# rf_txmix.net
KiCad netlist of a schematic drawn in Altium Designer
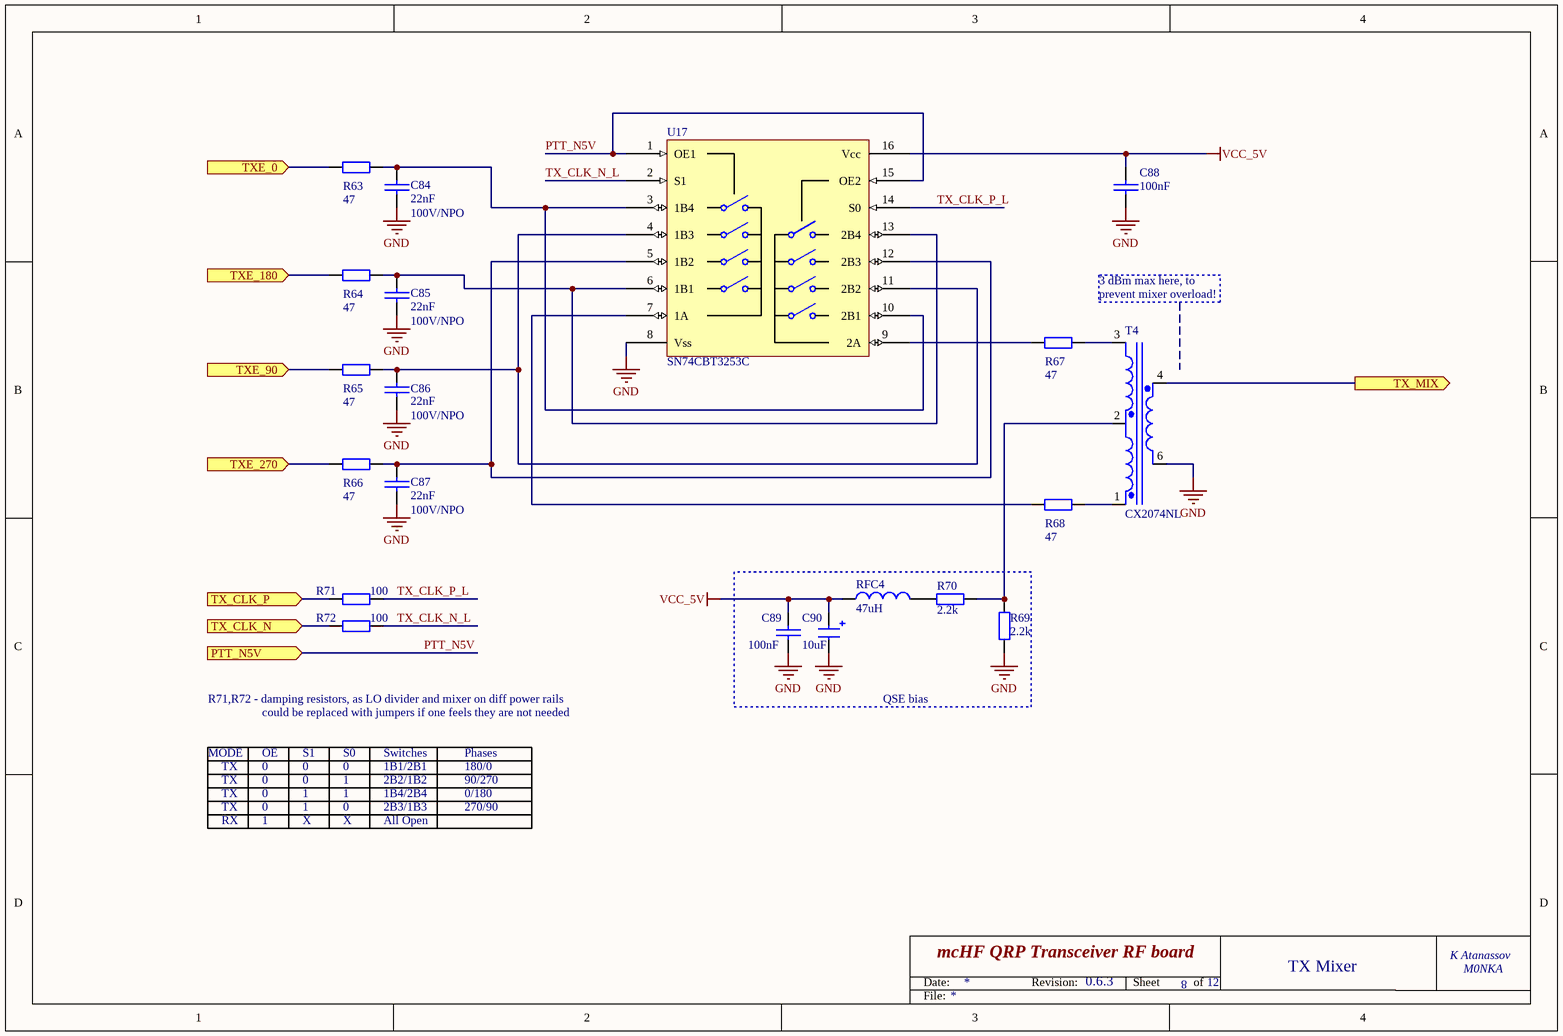
[diagram p0: rf_txmix.SchDoc]

(export (version "E")
  (design (tool "Eeschema 10.0.6"))
  (components
    (comp (ref "C84")
      (value "22nF")
      (footprint "CAP_B")
      (description "Capacitor")
      (fields (field (name "VOLTAGE") "100V/NPO"))
      (libsource (lib "mcHF_rf") (part "CAP"))
    )
    (comp (ref "C85")
      (value "22nF")
      (footprint "CAP_B")
      (description "Capacitor")
      (fields (field (name "VOLTAGE") "100V/NPO"))
      (libsource (lib "mcHF_rf") (part "CAP"))
    )
    (comp (ref "C86")
      (value "22nF")
      (footprint "CAP_B")
      (description "Capacitor")
      (fields (field (name "VOLTAGE") "100V/NPO"))
      (libsource (lib "mcHF_rf") (part "CAP"))
    )
    (comp (ref "C87")
      (value "22nF")
      (footprint "CAP_B")
      (description "Capacitor")
      (fields (field (name "VOLTAGE") "100V/NPO"))
      (libsource (lib "mcHF_rf") (part "CAP"))
    )
    (comp (ref "C88")
      (value "100nF")
      (footprint "0805-Pro")
      (description "Capacitor")
      (libsource (lib "mcHF_rf") (part "CAP"))
    )
    (comp (ref "C89")
      (value "100nF")
      (footprint "0805-Pro")
      (description "Capacitor")
      (libsource (lib "mcHF_rf") (part "CAP"))
    )
    (comp (ref "C90")
      (value "10uF")
      (footprint "1206_Elec_Cap_N")
      (description "Electrolitic capacitor")
      (libsource (lib "mcHF_rf") (part "CAP-POL"))
    )
    (comp (ref "R63")
      (value "47")
      (footprint "0805-Pro")
      (description "Resistor")
      (libsource (lib "") (part "RES_1"))
    )
    (comp (ref "R64")
      (value "47")
      (footprint "0805-Pro")
      (description "Resistor")
      (libsource (lib "") (part "RES_1"))
    )
    (comp (ref "R65")
      (value "47")
      (footprint "0805-Pro")
      (description "Resistor")
      (libsource (lib "") (part "RES_1"))
    )
    (comp (ref "R66")
      (value "47")
      (footprint "0805-Pro")
      (description "Resistor")
      (libsource (lib "") (part "RES_1"))
    )
    (comp (ref "R67")
      (value "47")
      (footprint "0805-Pro")
      (description "Resistor")
      (libsource (lib "") (part "RES_1"))
    )
    (comp (ref "R68")
      (value "47")
      (footprint "0805-Pro")
      (description "Resistor")
      (libsource (lib "") (part "RES_1"))
    )
    (comp (ref "R69")
      (value "2.2k")
      (footprint "0805-Pro")
      (description "Resistor")
      (libsource (lib "") (part "RES_2"))
    )
    (comp (ref "R70")
      (value "2.2k")
      (footprint "0805-Pro")
      (description "Resistor")
      (libsource (lib "mcHF_rf") (part "RES"))
    )
    (comp (ref "R71")
      (value "100")
      (footprint "0805-Pro")
      (description "Resistor")
      (libsource (lib "mcHF_rf") (part "RES"))
    )
    (comp (ref "R72")
      (value "100")
      (footprint "0805-Pro")
      (description "Resistor")
      (libsource (lib "mcHF_rf") (part "RES"))
    )
    (comp (ref "RFC4")
      (value "47uH")
      (footprint "0805-Pro")
      (description "INDUCTOR, SIGNAL LINE, 4.7UH, 1005")
      (libsource (lib "mcHF_rf") (part "TDK-NLV25T"))
    )
    (comp (ref "T4")
      (value "CX2074NL")
      (footprint "SOP5_NEW1")
      (description "Wideband RF Transformer 1:4")
      (libsource (lib "mcHF_rf") (part "CX2074NL"))
    )
    (comp (ref "U17")
      (value "SN74CBT3253C")
      (footprint "SO-16-Pro")
      (description "Dual 4:1 Demux/Analog Switch")
      (libsource (lib "mcHF_rf") (part "SN74CBT3253C"))
    )
  )
  (nets
    (net (code "1") (name "/PTT_N5V") (class "Default")
      (node (ref "U17") (pin "1") (pinfunction "OE1_1") (pintype "input"))
      (node (ref "U17") (pin "15") (pinfunction "OE2_15") (pintype "input"))
    )
    (net (code "2") (name "/TXE_0") (class "Default")
      (node (ref "R63") (pin "1") (pinfunction "1_1") (pintype "passive"))
    )
    (net (code "3") (name "/TXE_90") (class "Default")
      (node (ref "R65") (pin "1") (pinfunction "1_1") (pintype "passive"))
    )
    (net (code "4") (name "/TXE_180") (class "Default")
      (node (ref "R64") (pin "1") (pinfunction "1_1") (pintype "passive"))
    )
    (net (code "5") (name "/TXE_270") (class "Default")
      (node (ref "R66") (pin "1") (pinfunction "1_1") (pintype "passive"))
    )
    (net (code "6") (name "/TX_CLK_N") (class "Default")
      (node (ref "R72") (pin "2") (pinfunction "2_2") (pintype "passive"))
    )
    (net (code "7") (name "/TX_CLK_N_L") (class "Default")
      (node (ref "R72") (pin "1") (pinfunction "1_1") (pintype "passive"))
      (node (ref "U17") (pin "2") (pinfunction "S1_2") (pintype "input"))
    )
    (net (code "8") (name "/TX_CLK_P") (class "Default")
      (node (ref "R71") (pin "2") (pinfunction "2_2") (pintype "passive"))
    )
    (net (code "9") (name "/TX_CLK_P_L") (class "Default")
      (node (ref "R71") (pin "1") (pinfunction "1_1") (pintype "passive"))
      (node (ref "U17") (pin "14") (pinfunction "S0_14") (pintype "input"))
    )
    (net (code "10") (name "/TX_MIX") (class "Default")
      (node (ref "T4") (pin "4") (pinfunction "Pri-_4") (pintype "passive"))
    )
    (net (code "11") (name "GND") (class "Default")
      (node (ref "C84") (pin "2") (pinfunction "2_2") (pintype "passive"))
      (node (ref "C85") (pin "2") (pinfunction "2_2") (pintype "passive"))
      (node (ref "C86") (pin "2") (pinfunction "2_2") (pintype "passive"))
      (node (ref "C87") (pin "2") (pinfunction "2_2") (pintype "passive"))
      (node (ref "C88") (pin "1") (pinfunction "1_1") (pintype "passive"))
      (node (ref "C89") (pin "1") (pinfunction "1_1") (pintype "passive"))
      (node (ref "C90") (pin "2") (pinfunction "2_2") (pintype "passive"))
      (node (ref "R69") (pin "1") (pinfunction "1_1") (pintype "passive"))
      (node (ref "T4") (pin "6") (pinfunction "Pri+_6") (pintype "passive"))
      (node (ref "U17") (pin "8") (pinfunction "Vss_8") (pintype "power_in"))
    )
    (net (code "12") (name "Net-(R70-Pad2)") (class "Default")
      (node (ref "R70") (pin "2") (pinfunction "2_2") (pintype "passive"))
      (node (ref "RFC4") (pin "2") (pinfunction "2_2") (pintype "passive"))
    )
    (net (code "13") (name "Net-(T4-Sec0)") (class "Default")
      (node (ref "R68") (pin "2") (pinfunction "2_2") (pintype "passive"))
      (node (ref "T4") (pin "1") (pinfunction "Sec0_1") (pintype "passive"))
    )
    (net (code "14") (name "Net-(T4-Sec180)") (class "Default")
      (node (ref "R67") (pin "2") (pinfunction "2_2") (pintype "passive"))
      (node (ref "T4") (pin "3") (pinfunction "Sec180_3") (pintype "passive"))
    )
    (net (code "15") (name "Net-(T4-SecCmn)") (class "Default")
      (node (ref "R69") (pin "2") (pinfunction "2_2") (pintype "passive"))
      (node (ref "R70") (pin "1") (pinfunction "1_1") (pintype "passive"))
      (node (ref "T4") (pin "2") (pinfunction "SecCmn_2") (pintype "passive"))
    )
    (net (code "16") (name "Net-(U17-1A)") (class "Default")
      (node (ref "R68") (pin "1") (pinfunction "1_1") (pintype "passive"))
      (node (ref "U17") (pin "7") (pinfunction "1A_7") (pintype "bidirectional"))
    )
    (net (code "17") (name "Net-(U17-1B1)") (class "Default")
      (node (ref "C85") (pin "1") (pinfunction "1_1") (pintype "passive"))
      (node (ref "R64") (pin "2") (pinfunction "2_2") (pintype "passive"))
      (node (ref "U17") (pin "13") (pinfunction "2B4_13") (pintype "bidirectional"))
      (node (ref "U17") (pin "6") (pinfunction "1B1_6") (pintype "bidirectional"))
    )
    (net (code "18") (name "Net-(U17-1B2)") (class "Default")
      (node (ref "C87") (pin "1") (pinfunction "1_1") (pintype "passive"))
      (node (ref "R66") (pin "2") (pinfunction "2_2") (pintype "passive"))
      (node (ref "U17") (pin "12") (pinfunction "2B3_12") (pintype "bidirectional"))
      (node (ref "U17") (pin "5") (pinfunction "1B2_5") (pintype "bidirectional"))
    )
    (net (code "19") (name "Net-(U17-1B3)") (class "Default")
      (node (ref "C86") (pin "1") (pinfunction "1_1") (pintype "passive"))
      (node (ref "R65") (pin "2") (pinfunction "2_2") (pintype "passive"))
      (node (ref "U17") (pin "11") (pinfunction "2B2_11") (pintype "bidirectional"))
      (node (ref "U17") (pin "4") (pinfunction "1B3_4") (pintype "bidirectional"))
    )
    (net (code "20") (name "Net-(U17-1B4)") (class "Default")
      (node (ref "C84") (pin "1") (pinfunction "1_1") (pintype "passive"))
      (node (ref "R63") (pin "2") (pinfunction "2_2") (pintype "passive"))
      (node (ref "U17") (pin "10") (pinfunction "2B1_10") (pintype "bidirectional"))
      (node (ref "U17") (pin "3") (pinfunction "1B4_3") (pintype "bidirectional"))
    )
    (net (code "21") (name "Net-(U17-2A)") (class "Default")
      (node (ref "R67") (pin "1") (pinfunction "1_1") (pintype "passive"))
      (node (ref "U17") (pin "9") (pinfunction "2A_9") (pintype "bidirectional"))
    )
    (net (code "22") (name "VCC_5V") (class "Default")
      (node (ref "C88") (pin "2") (pinfunction "2_2") (pintype "passive"))
      (node (ref "C89") (pin "2") (pinfunction "2_2") (pintype "passive"))
      (node (ref "C90") (pin "1") (pinfunction "1_1") (pintype "passive"))
      (node (ref "RFC4") (pin "1") (pinfunction "1_1") (pintype "passive"))
      (node (ref "U17") (pin "16") (pinfunction "Vcc_16") (pintype "power_in"))
    )
  )
)
